# NuEVI.net
KiCad netlist of a schematic drawn in EAGLE
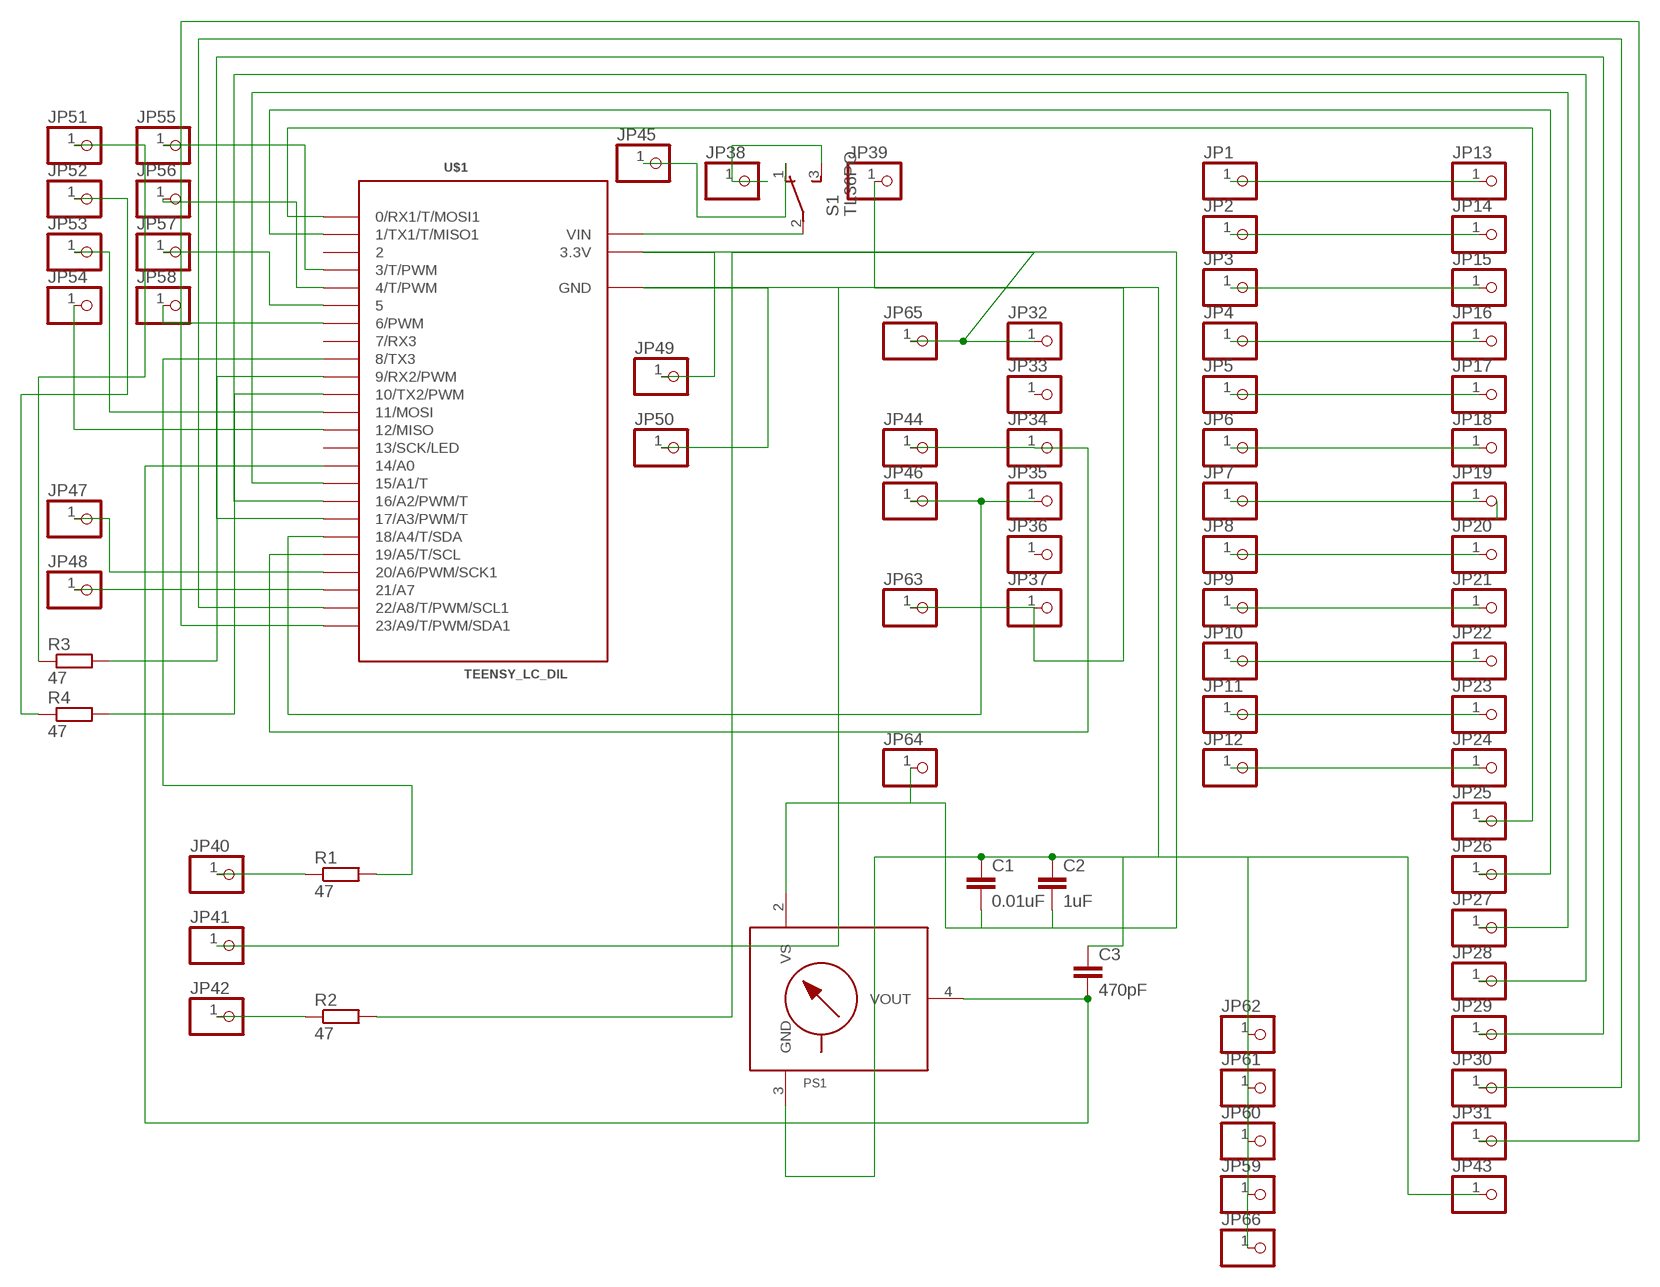
[diagram p0: schematic, sheet 1]

(export (version "E")
  (design (tool "Eeschema 10.0.6"))
  (components
    (comp (ref "C1")
      (value "0.01uF")
      (footprint "eagle-import:C050-024X044")
      (libsource (lib "eagle-import") (part "C-EU050-024X044"))
    )
    (comp (ref "C2")
      (value "1uF")
      (footprint "eagle-import:C050-024X044")
      (libsource (lib "eagle-import") (part "C-EU050-024X044"))
    )
    (comp (ref "C3")
      (value "470pF")
      (footprint "eagle-import:C050-024X044")
      (libsource (lib "eagle-import") (part "C-EU050-024X044"))
    )
    (comp (ref "JP1")
      (value "PINHD-1X1")
      (footprint "eagle-import:1X01")
      (libsource (lib "eagle-import") (part "PINHD-1X1"))
    )
    (comp (ref "JP2")
      (value "PINHD-1X1")
      (footprint "eagle-import:1X01")
      (libsource (lib "eagle-import") (part "PINHD-1X1"))
    )
    (comp (ref "JP3")
      (value "PINHD-1X1")
      (footprint "eagle-import:1X01")
      (libsource (lib "eagle-import") (part "PINHD-1X1"))
    )
    (comp (ref "JP4")
      (value "PINHD-1X1")
      (footprint "eagle-import:1X01")
      (libsource (lib "eagle-import") (part "PINHD-1X1"))
    )
    (comp (ref "JP5")
      (value "PINHD-1X1")
      (footprint "eagle-import:1X01")
      (libsource (lib "eagle-import") (part "PINHD-1X1"))
    )
    (comp (ref "JP6")
      (value "PINHD-1X1")
      (footprint "eagle-import:1X01")
      (libsource (lib "eagle-import") (part "PINHD-1X1"))
    )
    (comp (ref "JP7")
      (value "PINHD-1X1")
      (footprint "eagle-import:1X01")
      (libsource (lib "eagle-import") (part "PINHD-1X1"))
    )
    (comp (ref "JP8")
      (value "PINHD-1X1")
      (footprint "eagle-import:1X01")
      (libsource (lib "eagle-import") (part "PINHD-1X1"))
    )
    (comp (ref "JP9")
      (value "PINHD-1X1")
      (footprint "eagle-import:1X01")
      (libsource (lib "eagle-import") (part "PINHD-1X1"))
    )
    (comp (ref "JP10")
      (value "PINHD-1X1")
      (footprint "eagle-import:1X01")
      (libsource (lib "eagle-import") (part "PINHD-1X1"))
    )
    (comp (ref "JP11")
      (value "PINHD-1X1")
      (footprint "eagle-import:1X01")
      (libsource (lib "eagle-import") (part "PINHD-1X1"))
    )
    (comp (ref "JP12")
      (value "PINHD-1X1")
      (footprint "eagle-import:1X01")
      (libsource (lib "eagle-import") (part "PINHD-1X1"))
    )
    (comp (ref "JP13")
      (value "PINHD-1X1")
      (footprint "eagle-import:1X01")
      (libsource (lib "eagle-import") (part "PINHD-1X1"))
    )
    (comp (ref "JP14")
      (value "PINHD-1X1")
      (footprint "eagle-import:1X01")
      (libsource (lib "eagle-import") (part "PINHD-1X1"))
    )
    (comp (ref "JP15")
      (value "PINHD-1X1")
      (footprint "eagle-import:1X01")
      (libsource (lib "eagle-import") (part "PINHD-1X1"))
    )
    (comp (ref "JP16")
      (value "PINHD-1X1")
      (footprint "eagle-import:1X01")
      (libsource (lib "eagle-import") (part "PINHD-1X1"))
    )
    (comp (ref "JP17")
      (value "PINHD-1X1")
      (footprint "eagle-import:1X01")
      (libsource (lib "eagle-import") (part "PINHD-1X1"))
    )
    (comp (ref "JP18")
      (value "PINHD-1X1")
      (footprint "eagle-import:1X01")
      (libsource (lib "eagle-import") (part "PINHD-1X1"))
    )
    (comp (ref "JP19")
      (value "PINHD-1X1")
      (footprint "eagle-import:1X01")
      (libsource (lib "eagle-import") (part "PINHD-1X1"))
    )
    (comp (ref "JP20")
      (value "PINHD-1X1")
      (footprint "eagle-import:1X01")
      (libsource (lib "eagle-import") (part "PINHD-1X1"))
    )
    (comp (ref "JP21")
      (value "PINHD-1X1")
      (footprint "eagle-import:1X01")
      (libsource (lib "eagle-import") (part "PINHD-1X1"))
    )
    (comp (ref "JP22")
      (value "PINHD-1X1")
      (footprint "eagle-import:1X01")
      (libsource (lib "eagle-import") (part "PINHD-1X1"))
    )
    (comp (ref "JP23")
      (value "PINHD-1X1")
      (footprint "eagle-import:1X01")
      (libsource (lib "eagle-import") (part "PINHD-1X1"))
    )
    (comp (ref "JP24")
      (value "PINHD-1X1")
      (footprint "eagle-import:1X01")
      (libsource (lib "eagle-import") (part "PINHD-1X1"))
    )
    (comp (ref "JP25")
      (value "PINHD-1X1")
      (footprint "eagle-import:1X01")
      (libsource (lib "eagle-import") (part "PINHD-1X1"))
    )
    (comp (ref "JP26")
      (value "PINHD-1X1")
      (footprint "eagle-import:1X01")
      (libsource (lib "eagle-import") (part "PINHD-1X1"))
    )
    (comp (ref "JP27")
      (value "PINHD-1X1")
      (footprint "eagle-import:1X01")
      (libsource (lib "eagle-import") (part "PINHD-1X1"))
    )
    (comp (ref "JP28")
      (value "PINHD-1X1")
      (footprint "eagle-import:1X01")
      (libsource (lib "eagle-import") (part "PINHD-1X1"))
    )
    (comp (ref "JP29")
      (value "PINHD-1X1")
      (footprint "eagle-import:1X01")
      (libsource (lib "eagle-import") (part "PINHD-1X1"))
    )
    (comp (ref "JP30")
      (value "PINHD-1X1")
      (footprint "eagle-import:1X01")
      (libsource (lib "eagle-import") (part "PINHD-1X1"))
    )
    (comp (ref "JP31")
      (value "PINHD-1X1")
      (footprint "eagle-import:1X01")
      (libsource (lib "eagle-import") (part "PINHD-1X1"))
    )
    (comp (ref "JP32")
      (value "PINHD-1X1")
      (footprint "eagle-import:1X01")
      (libsource (lib "eagle-import") (part "PINHD-1X1"))
    )
    (comp (ref "JP33")
      (value "PINHD-1X1")
      (footprint "eagle-import:1X01")
      (libsource (lib "eagle-import") (part "PINHD-1X1"))
    )
    (comp (ref "JP34")
      (value "PINHD-1X1")
      (footprint "eagle-import:1X01")
      (libsource (lib "eagle-import") (part "PINHD-1X1"))
    )
    (comp (ref "JP35")
      (value "PINHD-1X1")
      (footprint "eagle-import:1X01")
      (libsource (lib "eagle-import") (part "PINHD-1X1"))
    )
    (comp (ref "JP36")
      (value "PINHD-1X1")
      (footprint "eagle-import:1X01")
      (libsource (lib "eagle-import") (part "PINHD-1X1"))
    )
    (comp (ref "JP37")
      (value "PINHD-1X1")
      (footprint "eagle-import:1X01")
      (libsource (lib "eagle-import") (part "PINHD-1X1"))
    )
    (comp (ref "JP38")
      (value "PINHD-1X1")
      (footprint "eagle-import:1X01")
      (libsource (lib "eagle-import") (part "PINHD-1X1"))
    )
    (comp (ref "JP39")
      (value "PINHD-1X1")
      (footprint "eagle-import:1X01")
      (libsource (lib "eagle-import") (part "PINHD-1X1"))
    )
    (comp (ref "JP40")
      (value "PINHD-1X1")
      (footprint "eagle-import:1X01")
      (libsource (lib "eagle-import") (part "PINHD-1X1"))
    )
    (comp (ref "JP41")
      (value "PINHD-1X1")
      (footprint "eagle-import:1X01")
      (libsource (lib "eagle-import") (part "PINHD-1X1"))
    )
    (comp (ref "JP42")
      (value "PINHD-1X1")
      (footprint "eagle-import:1X01")
      (libsource (lib "eagle-import") (part "PINHD-1X1"))
    )
    (comp (ref "JP43")
      (value "PINHD-1X1")
      (footprint "eagle-import:1X01")
      (libsource (lib "eagle-import") (part "PINHD-1X1"))
    )
    (comp (ref "JP44")
      (value "PINHD-1X1")
      (footprint "eagle-import:1X01")
      (libsource (lib "eagle-import") (part "PINHD-1X1"))
    )
    (comp (ref "JP45")
      (value "PINHD-1X1")
      (footprint "eagle-import:1X01")
      (libsource (lib "eagle-import") (part "PINHD-1X1"))
    )
    (comp (ref "JP46")
      (value "PINHD-1X1")
      (footprint "eagle-import:1X01")
      (libsource (lib "eagle-import") (part "PINHD-1X1"))
    )
    (comp (ref "JP47")
      (value "PINHD-1X1")
      (footprint "eagle-import:1X01")
      (libsource (lib "eagle-import") (part "PINHD-1X1"))
    )
    (comp (ref "JP48")
      (value "PINHD-1X1")
      (footprint "eagle-import:1X01")
      (libsource (lib "eagle-import") (part "PINHD-1X1"))
    )
    (comp (ref "JP49")
      (value "PINHD-1X1")
      (footprint "eagle-import:1X01")
      (libsource (lib "eagle-import") (part "PINHD-1X1"))
    )
    (comp (ref "JP50")
      (value "PINHD-1X1")
      (footprint "eagle-import:1X01")
      (libsource (lib "eagle-import") (part "PINHD-1X1"))
    )
    (comp (ref "JP51")
      (value "PINHD-1X1")
      (footprint "eagle-import:1X01")
      (libsource (lib "eagle-import") (part "PINHD-1X1"))
    )
    (comp (ref "JP52")
      (value "PINHD-1X1")
      (footprint "eagle-import:1X01")
      (libsource (lib "eagle-import") (part "PINHD-1X1"))
    )
    (comp (ref "JP53")
      (value "PINHD-1X1")
      (footprint "eagle-import:1X01")
      (libsource (lib "eagle-import") (part "PINHD-1X1"))
    )
    (comp (ref "JP54")
      (value "PINHD-1X1")
      (footprint "eagle-import:1X01")
      (libsource (lib "eagle-import") (part "PINHD-1X1"))
    )
    (comp (ref "JP55")
      (value "PINHD-1X1")
      (footprint "eagle-import:1X01")
      (libsource (lib "eagle-import") (part "PINHD-1X1"))
    )
    (comp (ref "JP56")
      (value "PINHD-1X1")
      (footprint "eagle-import:1X01")
      (libsource (lib "eagle-import") (part "PINHD-1X1"))
    )
    (comp (ref "JP57")
      (value "PINHD-1X1")
      (footprint "eagle-import:1X01")
      (libsource (lib "eagle-import") (part "PINHD-1X1"))
    )
    (comp (ref "JP58")
      (value "PINHD-1X1")
      (footprint "eagle-import:1X01")
      (libsource (lib "eagle-import") (part "PINHD-1X1"))
    )
    (comp (ref "JP59")
      (value "PINHD-1X1")
      (footprint "eagle-import:1X01")
      (libsource (lib "eagle-import") (part "PINHD-1X1"))
    )
    (comp (ref "JP60")
      (value "PINHD-1X1")
      (footprint "eagle-import:1X01")
      (libsource (lib "eagle-import") (part "PINHD-1X1"))
    )
    (comp (ref "JP61")
      (value "PINHD-1X1")
      (footprint "eagle-import:1X01")
      (libsource (lib "eagle-import") (part "PINHD-1X1"))
    )
    (comp (ref "JP62")
      (value "PINHD-1X1")
      (footprint "eagle-import:1X01")
      (libsource (lib "eagle-import") (part "PINHD-1X1"))
    )
    (comp (ref "JP63")
      (value "PINHD-1X1")
      (footprint "eagle-import:1X01")
      (libsource (lib "eagle-import") (part "PINHD-1X1"))
    )
    (comp (ref "JP64")
      (value "PINHD-1X1")
      (footprint "eagle-import:1X01")
      (libsource (lib "eagle-import") (part "PINHD-1X1"))
    )
    (comp (ref "JP65")
      (value "PINHD-1X1")
      (footprint "eagle-import:1X01")
      (libsource (lib "eagle-import") (part "PINHD-1X1"))
    )
    (comp (ref "JP66")
      (value "PINHD-1X1")
      (footprint "eagle-import:1X01")
      (libsource (lib "eagle-import") (part "PINHD-1X1"))
    )
    (comp (ref "PS1")
      (value "MPX-1369")
      (footprint "eagle-import:1369")
      (libsource (lib "eagle-import") (part "MPX-1369"))
    )
    (comp (ref "R1")
      (value "47")
      (footprint "eagle-import:0207_7")
      (libsource (lib "eagle-import") (part "R-EU_0207/7"))
    )
    (comp (ref "R2")
      (value "47")
      (footprint "eagle-import:0207_7")
      (libsource (lib "eagle-import") (part "R-EU_0207/7"))
    )
    (comp (ref "R3")
      (value "47")
      (footprint "eagle-import:0207_7")
      (libsource (lib "eagle-import") (part "R-EU_0207/7"))
    )
    (comp (ref "R4")
      (value "47")
      (footprint "eagle-import:0207_7")
      (libsource (lib "eagle-import") (part "R-EU_0207/7"))
    )
    (comp (ref "S1")
      (value "TL36PO")
      (footprint "eagle-import:TL3XPO")
      (libsource (lib "eagle-import") (part "TL36PO"))
    )
    (comp (ref "U$1")
      (value "TEENSY_LC_DIL")
      (footprint "eagle-import:TEENSY_3.0-3.2&LC_DIL")
      (libsource (lib "eagle-import") (part "TEENSY_LC_DIL"))
    )
  )
  (nets
    (net (code "1") (name "Net-(JP1-Pad1)") (class "Default")
      (node (ref "JP1") (pin "1") (pinfunction "1_1") (pintype "passive"))
      (node (ref "JP13") (pin "1") (pinfunction "1_1") (pintype "passive"))
    )
    (net (code "2") (name "Net-(JP10-Pad1)") (class "Default")
      (node (ref "JP10") (pin "1") (pinfunction "1_1") (pintype "passive"))
      (node (ref "JP22") (pin "1") (pinfunction "1_1") (pintype "passive"))
    )
    (net (code "3") (name "Net-(JP11-Pad1)") (class "Default")
      (node (ref "JP11") (pin "1") (pinfunction "1_1") (pintype "passive"))
      (node (ref "JP23") (pin "1") (pinfunction "1_1") (pintype "passive"))
    )
    (net (code "4") (name "Net-(JP12-Pad1)") (class "Default")
      (node (ref "JP12") (pin "1") (pinfunction "1_1") (pintype "passive"))
      (node (ref "JP24") (pin "1") (pinfunction "1_1") (pintype "passive"))
    )
    (net (code "5") (name "Net-(JP14-Pad1)") (class "Default")
      (node (ref "JP14") (pin "1") (pinfunction "1_1") (pintype "passive"))
      (node (ref "JP2") (pin "1") (pinfunction "1_1") (pintype "passive"))
    )
    (net (code "6") (name "Net-(JP15-Pad1)") (class "Default")
      (node (ref "JP15") (pin "1") (pinfunction "1_1") (pintype "passive"))
      (node (ref "JP3") (pin "1") (pinfunction "1_1") (pintype "passive"))
    )
    (net (code "7") (name "Net-(JP16-Pad1)") (class "Default")
      (node (ref "JP16") (pin "1") (pinfunction "1_1") (pintype "passive"))
      (node (ref "JP4") (pin "1") (pinfunction "1_1") (pintype "passive"))
    )
    (net (code "8") (name "Net-(JP17-Pad1)") (class "Default")
      (node (ref "JP17") (pin "1") (pinfunction "1_1") (pintype "passive"))
      (node (ref "JP5") (pin "1") (pinfunction "1_1") (pintype "passive"))
    )
    (net (code "9") (name "Net-(JP18-Pad1)") (class "Default")
      (node (ref "JP18") (pin "1") (pinfunction "1_1") (pintype "passive"))
      (node (ref "JP6") (pin "1") (pinfunction "1_1") (pintype "passive"))
    )
    (net (code "10") (name "Net-(JP19-Pad1)") (class "Default")
      (node (ref "JP19") (pin "1") (pinfunction "1_1") (pintype "passive"))
      (node (ref "JP7") (pin "1") (pinfunction "1_1") (pintype "passive"))
    )
    (net (code "11") (name "Net-(JP20-Pad1)") (class "Default")
      (node (ref "JP20") (pin "1") (pinfunction "1_1") (pintype "passive"))
      (node (ref "JP8") (pin "1") (pinfunction "1_1") (pintype "passive"))
    )
    (net (code "12") (name "Net-(JP21-Pad1)") (class "Default")
      (node (ref "JP21") (pin "1") (pinfunction "1_1") (pintype "passive"))
      (node (ref "JP9") (pin "1") (pinfunction "1_1") (pintype "passive"))
    )
    (net (code "13") (name "Net-(JP40-Pad1)") (class "Default")
      (node (ref "JP40") (pin "1") (pinfunction "1_1") (pintype "passive"))
      (node (ref "R1") (pin "1") (pinfunction "1_1") (pintype "passive"))
    )
    (net (code "14") (name "Net-(JP42-Pad1)") (class "Default")
      (node (ref "JP42") (pin "1") (pinfunction "1_1") (pintype "passive"))
      (node (ref "R2") (pin "1") (pinfunction "1_1") (pintype "passive"))
    )
    (net (code "15") (name "Net-(JP48-Pad1)") (class "Default")
      (node (ref "JP48") (pin "1") (pinfunction "1_1") (pintype "passive"))
      (node (ref "U$1") (pin "21/A7") (pinfunction "21/A7_21/A7") (pintype "bidirectional"))
    )
    (net (code "16") (name "Net-(JP51-Pad1)") (class "Default")
      (node (ref "JP51") (pin "1") (pinfunction "1_1") (pintype "passive"))
      (node (ref "R3") (pin "1") (pinfunction "1_1") (pintype "passive"))
    )
    (net (code "17") (name "Net-(JP52-Pad1)") (class "Default")
      (node (ref "JP52") (pin "1") (pinfunction "1_1") (pintype "passive"))
      (node (ref "R4") (pin "1") (pinfunction "1_1") (pintype "passive"))
    )
    (net (code "18") (name "Net-(JP57-Pad1)") (class "Default")
      (node (ref "JP57") (pin "1") (pinfunction "1_1") (pintype "passive"))
      (node (ref "U$1") (pin "5") (pinfunction "5_5") (pintype "bidirectional"))
    )
    (net (code "19") (name "Net-(PS1-GND)") (class "Default")
      (node (ref "C1") (pin "1") (pinfunction "1_1") (pintype "passive"))
      (node (ref "C2") (pin "1") (pinfunction "1_1") (pintype "passive"))
      (node (ref "C3") (pin "1") (pinfunction "1_1") (pintype "passive"))
      (node (ref "JP37") (pin "1") (pinfunction "1_1") (pintype "passive"))
      (node (ref "JP39") (pin "1") (pinfunction "1_1") (pintype "passive"))
      (node (ref "JP41") (pin "1") (pinfunction "1_1") (pintype "passive"))
      (node (ref "JP43") (pin "1") (pinfunction "1_1") (pintype "passive"))
      (node (ref "JP50") (pin "1") (pinfunction "1_1") (pintype "passive"))
      (node (ref "JP59") (pin "1") (pinfunction "1_1") (pintype "passive"))
      (node (ref "JP60") (pin "1") (pinfunction "1_1") (pintype "passive"))
      (node (ref "JP61") (pin "1") (pinfunction "1_1") (pintype "passive"))
      (node (ref "JP62") (pin "1") (pinfunction "1_1") (pintype "passive"))
      (node (ref "JP63") (pin "1") (pinfunction "1_1") (pintype "passive"))
      (node (ref "JP66") (pin "1") (pinfunction "1_1") (pintype "passive"))
      (node (ref "PS1") (pin "3") (pinfunction "GND_3") (pintype "power_in"))
      (node (ref "U$1") (pin "AGND") (pinfunction "GND_AGND") (pintype "power_in"))
      (node (ref "U$1") (pin "GND") (pinfunction "GND_GND") (pintype "power_in"))
    )
    (net (code "20") (name "Net-(PS1-VOUT)") (class "Default")
      (node (ref "C3") (pin "2") (pinfunction "2_2") (pintype "passive"))
      (node (ref "PS1") (pin "4") (pinfunction "VOUT_4") (pintype "output"))
      (node (ref "U$1") (pin "14/A0") (pinfunction "14/A0_14/A0") (pintype "bidirectional"))
    )
    (net (code "21") (name "Net-(PS1-VS)") (class "Default")
      (node (ref "C1") (pin "2") (pinfunction "2_2") (pintype "passive"))
      (node (ref "C2") (pin "2") (pinfunction "2_2") (pintype "passive"))
      (node (ref "JP32") (pin "1") (pinfunction "1_1") (pintype "passive"))
      (node (ref "JP49") (pin "1") (pinfunction "1_1") (pintype "passive"))
      (node (ref "JP64") (pin "1") (pinfunction "1_1") (pintype "passive"))
      (node (ref "JP65") (pin "1") (pinfunction "1_1") (pintype "passive"))
      (node (ref "PS1") (pin "2") (pinfunction "VS_2") (pintype "power_in"))
      (node (ref "R2") (pin "2") (pinfunction "2_2") (pintype "passive"))
      (node (ref "U$1") (pin "3.3V") (pinfunction "3.3V_3.3V") (pintype "power_in"))
    )
    (net (code "22") (name "Net-(S1-O)") (class "Default")
      (node (ref "JP45") (pin "1") (pinfunction "1_1") (pintype "passive"))
      (node (ref "S1") (pin "1") (pinfunction "O_1") (pintype "passive"))
    )
    (net (code "23") (name "Net-(S1-P)") (class "Default")
      (node (ref "S1") (pin "2") (pinfunction "P_2") (pintype "passive"))
      (node (ref "U$1") (pin "VIN") (pinfunction "VIN_VIN") (pintype "power_in"))
    )
    (net (code "24") (name "Net-(S1-S)") (class "Default")
      (node (ref "JP38") (pin "1") (pinfunction "1_1") (pintype "passive"))
      (node (ref "S1") (pin "3") (pinfunction "S_3") (pintype "passive"))
    )
    (net (code "25") (name "Net-(U$1-0{slash}RX1{slash}T{slash}MOSI1)") (class "Default")
      (node (ref "JP25") (pin "1") (pinfunction "1_1") (pintype "passive"))
      (node (ref "U$1") (pin "0") (pinfunction "0/RX1/T/MOSI1_0") (pintype "bidirectional"))
    )
    (net (code "26") (name "Net-(U$1-1{slash}TX1{slash}T{slash}MISO1)") (class "Default")
      (node (ref "JP26") (pin "1") (pinfunction "1_1") (pintype "passive"))
      (node (ref "U$1") (pin "1") (pinfunction "1/TX1/T/MISO1_1") (pintype "bidirectional"))
    )
    (net (code "27") (name "Net-(U$1-3{slash}T{slash}PWM)") (class "Default")
      (node (ref "JP55") (pin "1") (pinfunction "1_1") (pintype "passive"))
      (node (ref "U$1") (pin "3") (pinfunction "3/T/PWM_3") (pintype "bidirectional"))
    )
    (net (code "28") (name "Net-(U$1-4{slash}T{slash}PWM)") (class "Default")
      (node (ref "JP56") (pin "1") (pinfunction "1_1") (pintype "passive"))
      (node (ref "U$1") (pin "4") (pinfunction "4/T/PWM_4") (pintype "bidirectional"))
    )
    (net (code "29") (name "Net-(U$1-6{slash}PWM)") (class "Default")
      (node (ref "JP58") (pin "1") (pinfunction "1_1") (pintype "passive"))
      (node (ref "U$1") (pin "6") (pinfunction "6/PWM_6") (pintype "bidirectional"))
    )
    (net (code "30") (name "Net-(U$1-8{slash}TX3)") (class "Default")
      (node (ref "R1") (pin "2") (pinfunction "2_2") (pintype "passive"))
      (node (ref "U$1") (pin "8") (pinfunction "8/TX3_8") (pintype "bidirectional"))
    )
    (net (code "31") (name "Net-(U$1-9{slash}RX2{slash}PWM)") (class "Default")
      (node (ref "R3") (pin "2") (pinfunction "2_2") (pintype "passive"))
      (node (ref "U$1") (pin "9") (pinfunction "9/RX2/PWM_9") (pintype "bidirectional"))
    )
    (net (code "32") (name "Net-(U$1-10{slash}TX2{slash}PWM)") (class "Default")
      (node (ref "R4") (pin "2") (pinfunction "2_2") (pintype "passive"))
      (node (ref "U$1") (pin "10") (pinfunction "10/TX2/PWM_10") (pintype "bidirectional"))
    )
    (net (code "33") (name "Net-(U$1-11{slash}MOSI)") (class "Default")
      (node (ref "JP53") (pin "1") (pinfunction "1_1") (pintype "passive"))
      (node (ref "U$1") (pin "11") (pinfunction "11/MOSI_11") (pintype "bidirectional"))
    )
    (net (code "34") (name "Net-(U$1-12{slash}MISO)") (class "Default")
      (node (ref "JP54") (pin "1") (pinfunction "1_1") (pintype "passive"))
      (node (ref "U$1") (pin "12") (pinfunction "12/MISO_12") (pintype "bidirectional"))
    )
    (net (code "35") (name "Net-(U$1-15{slash}A1{slash}T)") (class "Default")
      (node (ref "JP27") (pin "1") (pinfunction "1_1") (pintype "passive"))
      (node (ref "U$1") (pin "15/A1") (pinfunction "15/A1/T_15/A1") (pintype "bidirectional"))
    )
    (net (code "36") (name "Net-(U$1-16{slash}A2{slash}PWM{slash}T)") (class "Default")
      (node (ref "JP28") (pin "1") (pinfunction "1_1") (pintype "passive"))
      (node (ref "U$1") (pin "16/A2") (pinfunction "16/A2/PWM/T_16/A2") (pintype "bidirectional"))
    )
    (net (code "37") (name "Net-(U$1-17{slash}A3{slash}PWM{slash}T)") (class "Default")
      (node (ref "JP29") (pin "1") (pinfunction "1_1") (pintype "passive"))
      (node (ref "U$1") (pin "17/A3") (pinfunction "17/A3/PWM/T_17/A3") (pintype "bidirectional"))
    )
    (net (code "38") (name "Net-(U$1-18{slash}A4{slash}T{slash}SDA)") (class "Default")
      (node (ref "JP35") (pin "1") (pinfunction "1_1") (pintype "passive"))
      (node (ref "JP46") (pin "1") (pinfunction "1_1") (pintype "passive"))
      (node (ref "U$1") (pin "18/A4") (pinfunction "18/A4/T/SDA_18/A4") (pintype "bidirectional"))
    )
    (net (code "39") (name "Net-(U$1-19{slash}A5{slash}T{slash}SCL)") (class "Default")
      (node (ref "JP34") (pin "1") (pinfunction "1_1") (pintype "passive"))
      (node (ref "JP44") (pin "1") (pinfunction "1_1") (pintype "passive"))
      (node (ref "U$1") (pin "19/A5") (pinfunction "19/A5/T/SCL_19/A5") (pintype "bidirectional"))
    )
    (net (code "40") (name "Net-(U$1-20{slash}A6{slash}PWM{slash}SCK1)") (class "Default")
      (node (ref "JP47") (pin "1") (pinfunction "1_1") (pintype "passive"))
      (node (ref "U$1") (pin "20/A6") (pinfunction "20/A6/PWM/SCK1_20/A6") (pintype "bidirectional"))
    )
    (net (code "41") (name "Net-(U$1-22{slash}A8{slash}T{slash}PWM{slash}SCL1)") (class "Default")
      (node (ref "JP30") (pin "1") (pinfunction "1_1") (pintype "passive"))
      (node (ref "U$1") (pin "22/A8") (pinfunction "22/A8/T/PWM/SCL1_22/A8") (pintype "bidirectional"))
    )
    (net (code "42") (name "Net-(U$1-23{slash}A9{slash}T{slash}PWM{slash}SDA1)") (class "Default")
      (node (ref "JP31") (pin "1") (pinfunction "1_1") (pintype "passive"))
      (node (ref "U$1") (pin "23/A9") (pinfunction "23/A9/T/PWM/SDA1_23/A9") (pintype "bidirectional"))
    )
    (net (code "43") (name "unconnected-(JP33-Pad1)") (class "Default")
      (node (ref "JP33") (pin "1") (pinfunction "1_1") (pintype "passive"))
    )
    (net (code "44") (name "unconnected-(JP36-Pad1)") (class "Default")
      (node (ref "JP36") (pin "1") (pinfunction "1_1") (pintype "passive"))
    )
    (net (code "45") (name "unconnected-(PS1-NC-Pad1)") (class "Default")
      (node (ref "PS1") (pin "1") (pinfunction "NC_1") (pintype "no_connect"))
    )
    (net (code "46") (name "unconnected-(PS1-NC-Pad5)") (class "Default")
      (node (ref "PS1") (pin "5") (pinfunction "NC_5") (pintype "no_connect"))
    )
    (net (code "47") (name "unconnected-(PS1-NC-Pad6)") (class "Default")
      (node (ref "PS1") (pin "6") (pinfunction "NC_6") (pintype "no_connect"))
    )
    (net (code "48") (name "unconnected-(U$1-7{slash}RX3-Pad7)") (class "Default")
      (node (ref "U$1") (pin "7") (pinfunction "7/RX3_7") (pintype "bidirectional"))
    )
    (net (code "49") (name "unconnected-(U$1-13{slash}SCK{slash}LED-Pad13)") (class "Default")
      (node (ref "U$1") (pin "13") (pinfunction "13/SCK/LED_13") (pintype "bidirectional"))
    )
    (net (code "50") (name "unconnected-(U$1-Pad2)") (class "Default")
      (node (ref "U$1") (pin "2") (pinfunction "2_2") (pintype "bidirectional"))
    )
  )
)
